# MIDI_CV_0_222.net
KiCad netlist of a schematic drawn in EAGLE
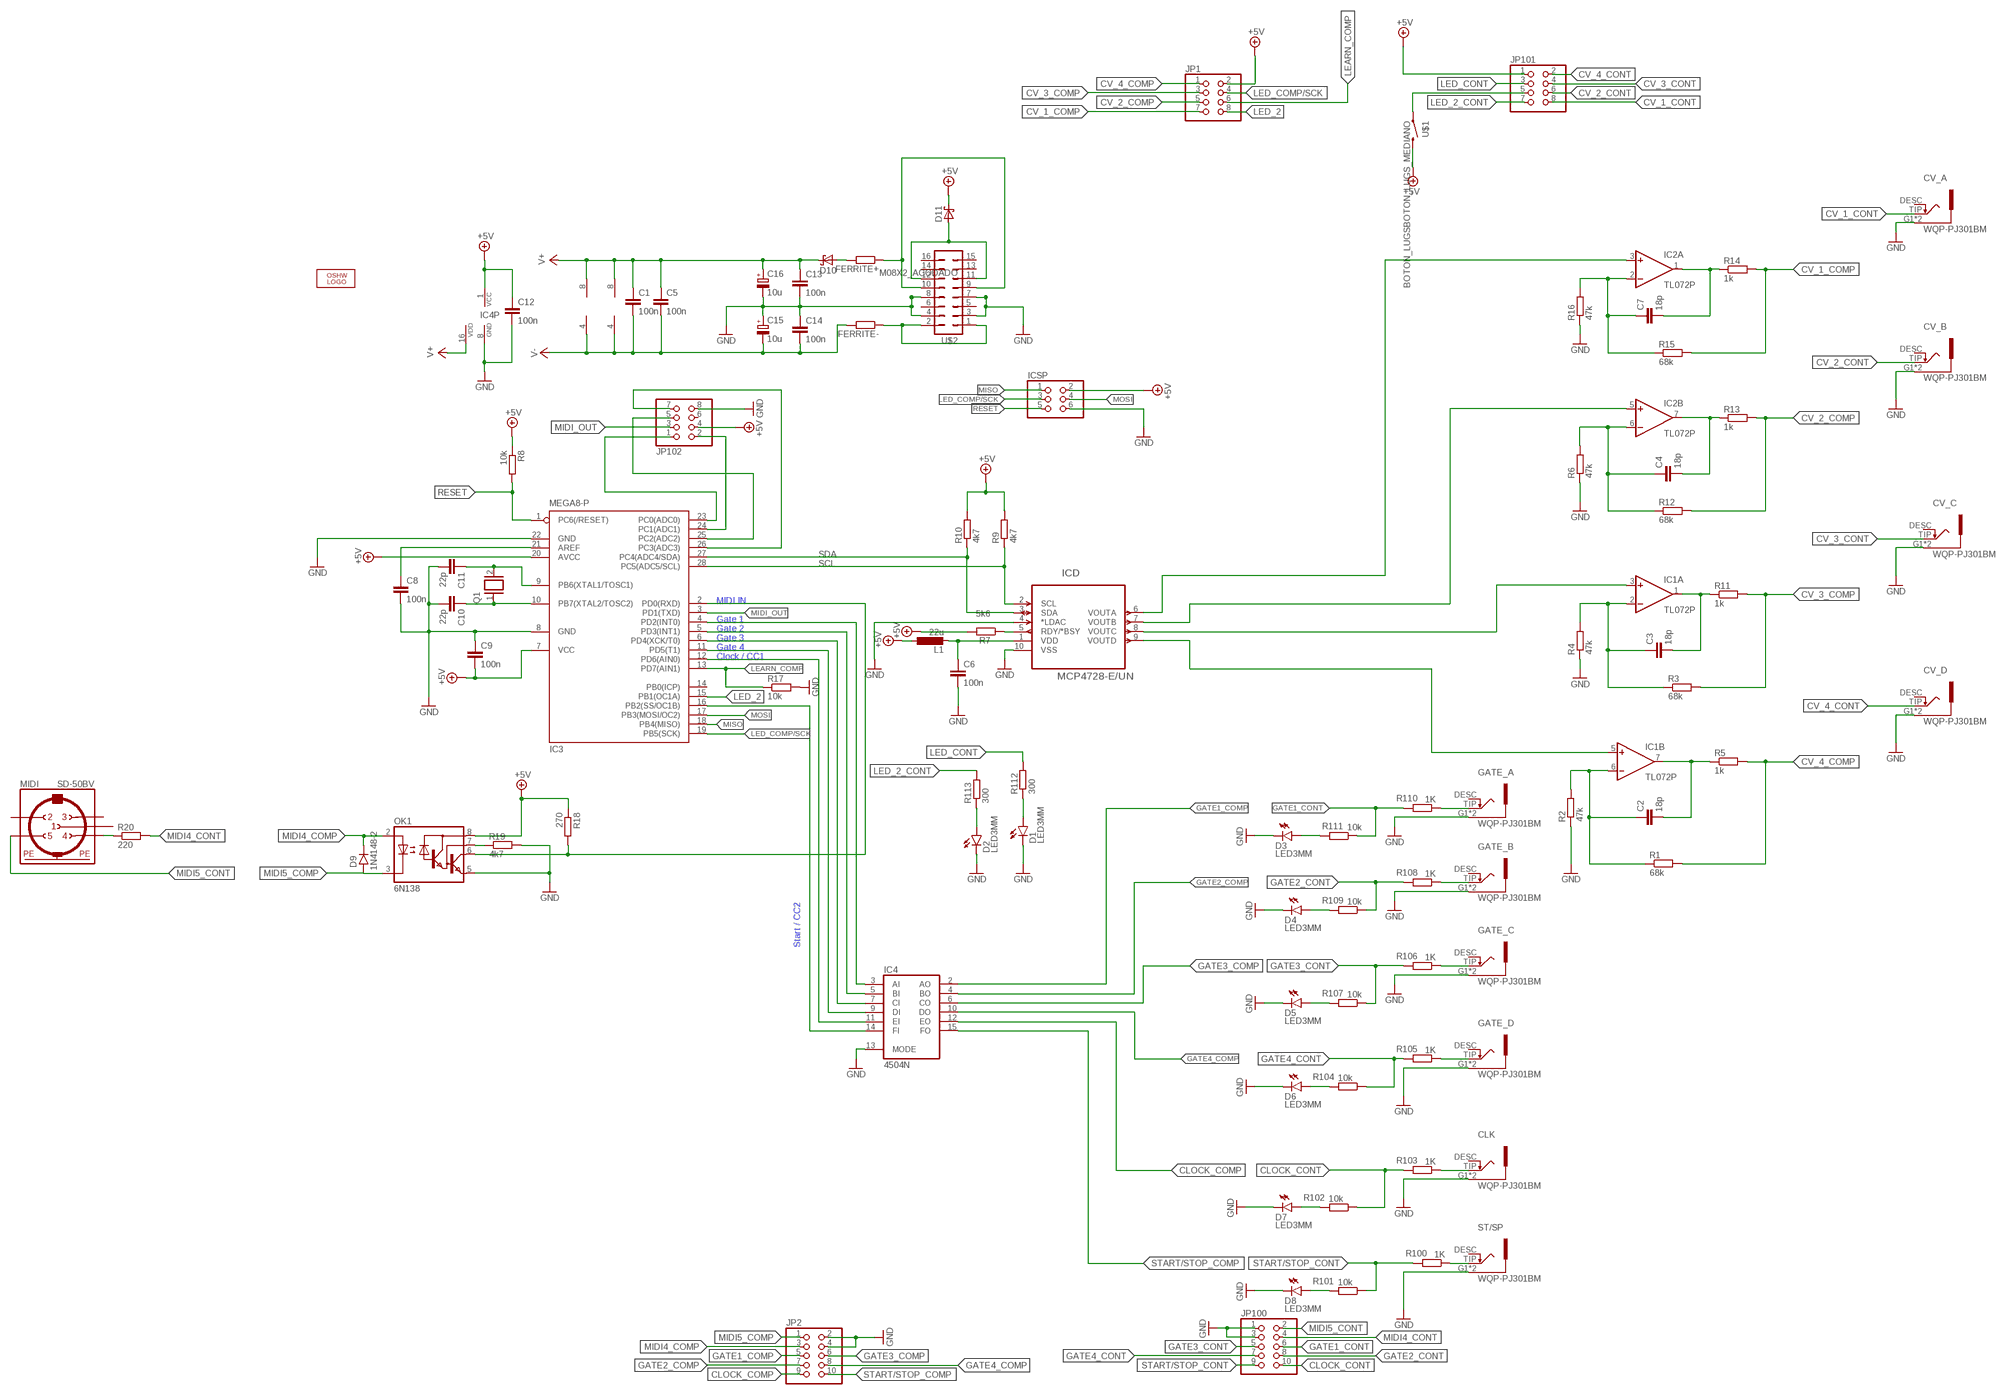
[diagram p0: schematic, sheet 1]

(export (version "E")
  (design (tool "Eeschema 10.0.6"))
  (components
    (comp (ref "$1_35_$")
      (value "OSHW_LOGO_FILLX0200-NT")
      (footprint "eagle-import:OSHW_FILLX200_NOTEXT")
      (libsource (lib "eagle-import") (part "OSHW_LOGO_FILLX0200-NT"))
    )
    (comp (ref "C1")
      (value "100n")
      (footprint "eagle-import:C050-025X075")
      (libsource (lib "eagle-import") (part "C-EU050-025X075"))
    )
    (comp (ref "C2")
      (value "18p")
      (footprint "eagle-import:C050-025X075")
      (libsource (lib "eagle-import") (part "C-EU050-025X075"))
    )
    (comp (ref "C3")
      (value "18p")
      (footprint "eagle-import:C050-025X075")
      (libsource (lib "eagle-import") (part "C-EU050-025X075"))
    )
    (comp (ref "C4")
      (value "18p")
      (footprint "eagle-import:C050-025X075")
      (libsource (lib "eagle-import") (part "C-EU050-025X075"))
    )
    (comp (ref "C5")
      (value "100n")
      (footprint "eagle-import:C050-025X075")
      (libsource (lib "eagle-import") (part "C-EU050-025X075"))
    )
    (comp (ref "C6")
      (value "100n")
      (footprint "eagle-import:C050-025X075")
      (libsource (lib "eagle-import") (part "C-EU050-025X075"))
    )
    (comp (ref "C7")
      (value "18p")
      (footprint "eagle-import:C050-025X075")
      (libsource (lib "eagle-import") (part "C-EU050-025X075"))
    )
    (comp (ref "C8")
      (value "100n")
      (footprint "eagle-import:C050-025X075")
      (libsource (lib "eagle-import") (part "C-EU050-025X075"))
    )
    (comp (ref "C9")
      (value "100n")
      (footprint "eagle-import:C050-025X075")
      (libsource (lib "eagle-import") (part "C-EU050-025X075"))
    )
    (comp (ref "C10")
      (value "22p")
      (footprint "eagle-import:C050-025X075")
      (libsource (lib "eagle-import") (part "C-EU050-025X075"))
    )
    (comp (ref "C11")
      (value "22p")
      (footprint "eagle-import:C050-025X075")
      (libsource (lib "eagle-import") (part "C-EU050-025X075"))
    )
    (comp (ref "C12")
      (value "100n")
      (footprint "eagle-import:C050-025X075")
      (libsource (lib "eagle-import") (part "C-EU050-025X075"))
    )
    (comp (ref "C13")
      (value "100n")
      (footprint "eagle-import:C050-025X075")
      (libsource (lib "eagle-import") (part "C-EU050-025X075"))
    )
    (comp (ref "C14")
      (value "100n")
      (footprint "eagle-import:C050-025X075")
      (libsource (lib "eagle-import") (part "C-EU050-025X075"))
    )
    (comp (ref "C15")
      (value "10u")
      (footprint "eagle-import:E2-4")
      (libsource (lib "eagle-import") (part "CPOL-EUE2-4"))
    )
    (comp (ref "C16")
      (value "10u")
      (footprint "eagle-import:E2-4")
      (libsource (lib "eagle-import") (part "CPOL-EUE2-4"))
    )
    (comp (ref "CLK")
      (value "WQP-PJ301BM")
      (footprint "eagle-import:WQP-PJ301BM")
      (libsource (lib "eagle-import") (part "WQP-PJ301BM"))
    )
    (comp (ref "CV_A")
      (value "WQP-PJ301BM")
      (footprint "eagle-import:WQP-PJ301BM")
      (libsource (lib "eagle-import") (part "WQP-PJ301BM"))
    )
    (comp (ref "CV_B")
      (value "WQP-PJ301BM")
      (footprint "eagle-import:WQP-PJ301BM")
      (libsource (lib "eagle-import") (part "WQP-PJ301BM"))
    )
    (comp (ref "CV_C")
      (value "WQP-PJ301BM")
      (footprint "eagle-import:WQP-PJ301BM")
      (libsource (lib "eagle-import") (part "WQP-PJ301BM"))
    )
    (comp (ref "CV_D")
      (value "WQP-PJ301BM")
      (footprint "eagle-import:WQP-PJ301BM")
      (libsource (lib "eagle-import") (part "WQP-PJ301BM"))
    )
    (comp (ref "D1")
      (value "LED3MM")
      (footprint "eagle-import:LED3MM")
      (libsource (lib "eagle-import") (part "LED3MM"))
    )
    (comp (ref "D2")
      (value "LED3MM")
      (footprint "eagle-import:LED3MM")
      (libsource (lib "eagle-import") (part "LED3MM"))
    )
    (comp (ref "D3")
      (value "LED3MM")
      (footprint "eagle-import:LED3MM")
      (libsource (lib "eagle-import") (part "LED3MM"))
    )
    (comp (ref "D4")
      (value "LED3MM")
      (footprint "eagle-import:LED3MM")
      (libsource (lib "eagle-import") (part "LED3MM"))
    )
    (comp (ref "D5")
      (value "LED3MM")
      (footprint "eagle-import:LED3MM")
      (libsource (lib "eagle-import") (part "LED3MM"))
    )
    (comp (ref "D6")
      (value "LED3MM")
      (footprint "eagle-import:LED3MM")
      (libsource (lib "eagle-import") (part "LED3MM"))
    )
    (comp (ref "D7")
      (value "LED3MM")
      (footprint "eagle-import:LED3MM")
      (libsource (lib "eagle-import") (part "LED3MM"))
    )
    (comp (ref "D8")
      (value "LED3MM")
      (footprint "eagle-import:LED3MM")
      (libsource (lib "eagle-import") (part "LED3MM"))
    )
    (comp (ref "D9")
      (value "1N4148-2")
      (footprint "eagle-import:DO35-2")
      (libsource (lib "eagle-import") (part "1N4148-2"))
    )
    (comp (ref "D10")
      (value "SCHOTTKY-DIODEDO35-7")
      (footprint "eagle-import:DO35-7")
      (libsource (lib "eagle-import") (part "SCHOTTKY-DIODEDO35-7"))
    )
    (comp (ref "D11")
      (value "SCHOTTKY-DIODEDO35-7")
      (footprint "eagle-import:DO35-7")
      (libsource (lib "eagle-import") (part "SCHOTTKY-DIODEDO35-7"))
    )
    (comp (ref "FERRITE+")
      (value "R-EU_0204/5")
      (footprint "eagle-import:0204_5")
      (libsource (lib "eagle-import") (part "R-EU_0204/5"))
    )
    (comp (ref "FERRITE-")
      (value "R-EU_0204/5")
      (footprint "eagle-import:0204_5")
      (libsource (lib "eagle-import") (part "R-EU_0204/5"))
    )
    (comp (ref "GATE_A")
      (value "WQP-PJ301BM")
      (footprint "eagle-import:WQP-PJ301BM")
      (libsource (lib "eagle-import") (part "WQP-PJ301BM"))
    )
    (comp (ref "GATE_B")
      (value "WQP-PJ301BM")
      (footprint "eagle-import:WQP-PJ301BM")
      (libsource (lib "eagle-import") (part "WQP-PJ301BM"))
    )
    (comp (ref "GATE_C")
      (value "WQP-PJ301BM")
      (footprint "eagle-import:WQP-PJ301BM")
      (libsource (lib "eagle-import") (part "WQP-PJ301BM"))
    )
    (comp (ref "GATE_D")
      (value "WQP-PJ301BM")
      (footprint "eagle-import:WQP-PJ301BM")
      (libsource (lib "eagle-import") (part "WQP-PJ301BM"))
    )
    (comp (ref "IC1")
      (value "TL072P")
      (footprint "eagle-import:DIL08")
      (libsource (lib "eagle-import") (part "TL072P"))
    )
    (comp (ref "IC2")
      (value "TL072P")
      (footprint "eagle-import:DIL08")
      (libsource (lib "eagle-import") (part "TL072P"))
    )
    (comp (ref "IC3")
      (value "MEGA8-P")
      (footprint "eagle-import:DIL28-3")
      (libsource (lib "eagle-import") (part "MEGA8-P"))
    )
    (comp (ref "IC4")
      (value "4504N")
      (footprint "eagle-import:DIL16")
      (libsource (lib "eagle-import") (part "4504N"))
    )
    (comp (ref "ICD")
      (value "MCP4728-E/UN")
      (footprint "eagle-import:SOP50P490X110-10N")
      (libsource (lib "eagle-import") (part "MCP4728-E/UN"))
    )
    (comp (ref "ICSP")
      (value "PINHD-2X3")
      (footprint "eagle-import:2X03")
      (libsource (lib "eagle-import") (part "PINHD-2X3"))
    )
    (comp (ref "JP1")
      (value "PINHD-2X4")
      (footprint "eagle-import:2X04")
      (libsource (lib "eagle-import") (part "PINHD-2X4"))
    )
    (comp (ref "JP2")
      (value "PINHD-2X5")
      (footprint "eagle-import:2X05")
      (libsource (lib "eagle-import") (part "PINHD-2X5"))
    )
    (comp (ref "JP100")
      (value "PINHD-2X5")
      (footprint "eagle-import:2X05")
      (libsource (lib "eagle-import") (part "PINHD-2X5"))
    )
    (comp (ref "JP101")
      (value "PINHD-2X4")
      (footprint "eagle-import:2X04")
      (libsource (lib "eagle-import") (part "PINHD-2X4"))
    )
    (comp (ref "JP102")
      (value "PINHD-2X4")
      (footprint "eagle-import:2X04")
      (libsource (lib "eagle-import") (part "PINHD-2X4"))
    )
    (comp (ref "L1")
      (value "22u")
      (footprint "eagle-import:0204_7")
      (libsource (lib "eagle-import") (part "L-EU0204/7"))
    )
    (comp (ref "MIDI")
      (value "SD-50BV")
      (footprint "eagle-import:SD-50BV")
      (libsource (lib "eagle-import") (part "SD-50BV"))
    )
    (comp (ref "OK1")
      (value "6N138")
      (footprint "eagle-import:DIL08")
      (libsource (lib "eagle-import") (part "6N138"))
    )
    (comp (ref "Q1")
      (value "XTAL/S")
      (footprint "eagle-import:QS")
      (libsource (lib "eagle-import") (part "XTAL/S"))
    )
    (comp (ref "R1")
      (value "68k")
      (footprint "eagle-import:0204_5")
      (libsource (lib "eagle-import") (part "R-EU_0204/5"))
    )
    (comp (ref "R2")
      (value "47k")
      (footprint "eagle-import:0204_5")
      (libsource (lib "eagle-import") (part "R-EU_0204/5"))
    )
    (comp (ref "R3")
      (value "68k")
      (footprint "eagle-import:0204_5")
      (libsource (lib "eagle-import") (part "R-EU_0204/5"))
    )
    (comp (ref "R4")
      (value "47k")
      (footprint "eagle-import:0204_5")
      (libsource (lib "eagle-import") (part "R-EU_0204/5"))
    )
    (comp (ref "R5")
      (value "1k")
      (footprint "eagle-import:0204_5")
      (libsource (lib "eagle-import") (part "R-EU_0204/5"))
    )
    (comp (ref "R6")
      (value "47k")
      (footprint "eagle-import:0204_5")
      (libsource (lib "eagle-import") (part "R-EU_0204/5"))
    )
    (comp (ref "R7")
      (value "5k6")
      (footprint "eagle-import:0204_5")
      (libsource (lib "eagle-import") (part "R-EU_0204/5"))
    )
    (comp (ref "R8")
      (value "10k")
      (footprint "eagle-import:0204_5")
      (libsource (lib "eagle-import") (part "R-EU_0204/5"))
    )
    (comp (ref "R9")
      (value "4k7")
      (footprint "eagle-import:0204_5")
      (libsource (lib "eagle-import") (part "R-EU_0204/5"))
    )
    (comp (ref "R10")
      (value "4k7")
      (footprint "eagle-import:0204_5")
      (libsource (lib "eagle-import") (part "R-EU_0204/5"))
    )
    (comp (ref "R11")
      (value "1k")
      (footprint "eagle-import:0204_5")
      (libsource (lib "eagle-import") (part "R-EU_0204/5"))
    )
    (comp (ref "R12")
      (value "68k")
      (footprint "eagle-import:0204_5")
      (libsource (lib "eagle-import") (part "R-EU_0204/5"))
    )
    (comp (ref "R13")
      (value "1k")
      (footprint "eagle-import:0204_5")
      (libsource (lib "eagle-import") (part "R-EU_0204/5"))
    )
    (comp (ref "R14")
      (value "1k")
      (footprint "eagle-import:0204_5")
      (libsource (lib "eagle-import") (part "R-EU_0204/5"))
    )
    (comp (ref "R15")
      (value "68k")
      (footprint "eagle-import:0204_5")
      (libsource (lib "eagle-import") (part "R-EU_0204/5"))
    )
    (comp (ref "R16")
      (value "47k")
      (footprint "eagle-import:0204_5")
      (libsource (lib "eagle-import") (part "R-EU_0204/5"))
    )
    (comp (ref "R17")
      (value "10k")
      (footprint "eagle-import:0204_5")
      (libsource (lib "eagle-import") (part "R-EU_0204/5"))
    )
    (comp (ref "R18")
      (value "270")
      (footprint "eagle-import:0204_5")
      (libsource (lib "eagle-import") (part "R-EU_0204/5"))
    )
    (comp (ref "R19")
      (value "4k7")
      (footprint "eagle-import:0204_5")
      (libsource (lib "eagle-import") (part "R-EU_0204/5"))
    )
    (comp (ref "R20")
      (value "220")
      (footprint "eagle-import:0204_5")
      (libsource (lib "eagle-import") (part "R-EU_0204/5"))
    )
    (comp (ref "R100")
      (value "1K")
      (footprint "eagle-import:0204_5")
      (libsource (lib "eagle-import") (part "R-EU_0204/5"))
    )
    (comp (ref "R101")
      (value "10k")
      (footprint "eagle-import:0204_5")
      (libsource (lib "eagle-import") (part "R-EU_0204/5"))
    )
    (comp (ref "R102")
      (value "10k")
      (footprint "eagle-import:0204_5")
      (libsource (lib "eagle-import") (part "R-EU_0204/5"))
    )
    (comp (ref "R103")
      (value "1K")
      (footprint "eagle-import:0204_5")
      (libsource (lib "eagle-import") (part "R-EU_0204/5"))
    )
    (comp (ref "R104")
      (value "10k")
      (footprint "eagle-import:0204_5")
      (libsource (lib "eagle-import") (part "R-EU_0204/5"))
    )
    (comp (ref "R105")
      (value "1K")
      (footprint "eagle-import:0204_5")
      (libsource (lib "eagle-import") (part "R-EU_0204/5"))
    )
    (comp (ref "R106")
      (value "1K")
      (footprint "eagle-import:0204_5")
      (libsource (lib "eagle-import") (part "R-EU_0204/5"))
    )
    (comp (ref "R107")
      (value "10k")
      (footprint "eagle-import:0204_5")
      (libsource (lib "eagle-import") (part "R-EU_0204/5"))
    )
    (comp (ref "R108")
      (value "1K")
      (footprint "eagle-import:0204_5")
      (libsource (lib "eagle-import") (part "R-EU_0204/5"))
    )
    (comp (ref "R109")
      (value "10k")
      (footprint "eagle-import:0204_5")
      (libsource (lib "eagle-import") (part "R-EU_0204/5"))
    )
    (comp (ref "R110")
      (value "1K")
      (footprint "eagle-import:0204_5")
      (libsource (lib "eagle-import") (part "R-EU_0204/5"))
    )
    (comp (ref "R111")
      (value "10k")
      (footprint "eagle-import:0204_5")
      (libsource (lib "eagle-import") (part "R-EU_0204/5"))
    )
    (comp (ref "R112")
      (value "300")
      (footprint "eagle-import:0204_5")
      (libsource (lib "eagle-import") (part "R-EU_0204/5"))
    )
    (comp (ref "R113")
      (value "300")
      (footprint "eagle-import:0204_5")
      (libsource (lib "eagle-import") (part "R-EU_0204/5"))
    )
    (comp (ref "ST/SP")
      (value "WQP-PJ301BM")
      (footprint "eagle-import:WQP-PJ301BM")
      (libsource (lib "eagle-import") (part "WQP-PJ301BM"))
    )
    (comp (ref "U$1")
      (value "BOTON_LUGSBOTON_LUGS_MEDIANO")
      (footprint "eagle-import:BOTON_LUGS_MEDIANO")
      (libsource (lib "eagle-import") (part "BOTON_LUGSBOTON_LUGS_MEDIANO"))
    )
    (comp (ref "U$2")
      (value "M08X2_ACODADO")
      (footprint "eagle-import:2X8-POWER-ACODADO")
      (libsource (lib "eagle-import") (part "M08X2_ACODADO"))
    )
  )
  (nets
    (net (code "1") (name "+5V") (class "Default")
      (node (ref "C12") (pin "1") (pinfunction "1_1") (pintype "passive"))
      (node (ref "C9") (pin "2") (pinfunction "2_2") (pintype "passive"))
      (node (ref "D11") (pin "C") (pinfunction "C_C") (pintype "passive"))
      (node (ref "IC3") (pin "20") (pinfunction "AVCC_20") (pintype "power_in"))
      (node (ref "IC3") (pin "7") (pinfunction "VCC_7") (pintype "power_in"))
      (node (ref "IC4") (pin "1") (pinfunction "VCC_1") (pintype "power_in"))
      (node (ref "ICSP") (pin "2") (pinfunction "2_2") (pintype "passive"))
      (node (ref "JP1") (pin "2") (pinfunction "2_2") (pintype "passive"))
      (node (ref "JP101") (pin "1") (pinfunction "1_1") (pintype "passive"))
      (node (ref "JP102") (pin "4") (pinfunction "4_4") (pintype "passive"))
      (node (ref "L1") (pin "1") (pinfunction "1_1") (pintype "passive"))
      (node (ref "OK1") (pin "8") (pinfunction "VCC_8") (pintype "passive"))
      (node (ref "R10") (pin "2") (pinfunction "2_2") (pintype "passive"))
      (node (ref "R18") (pin "1") (pinfunction "1_1") (pintype "passive"))
      (node (ref "R7") (pin "2") (pinfunction "2_2") (pintype "passive"))
      (node (ref "R8") (pin "1") (pinfunction "1_1") (pintype "passive"))
      (node (ref "R9") (pin "2") (pinfunction "2_2") (pintype "passive"))
      (node (ref "U$1") (pin "P$2") (pinfunction "2_P$2") (pintype "passive"))
    )
    (net (code "2") (name "CLOCK_COMP") (class "Default")
      (node (ref "IC4") (pin "12") (pinfunction "EO_12") (pintype "output"))
      (node (ref "JP2") (pin "9") (pinfunction "9_9") (pintype "passive"))
    )
    (net (code "3") (name "CLOCK_CONT") (class "Default")
      (node (ref "JP100") (pin "10") (pinfunction "10_10") (pintype "passive"))
      (node (ref "R102") (pin "1") (pinfunction "1_1") (pintype "passive"))
      (node (ref "R103") (pin "2") (pinfunction "2_2") (pintype "passive"))
    )
    (net (code "4") (name "CV_1_COMP") (class "Default")
      (node (ref "JP1") (pin "7") (pinfunction "7_7") (pintype "passive"))
      (node (ref "R14") (pin "2") (pinfunction "2_2") (pintype "passive"))
      (node (ref "R15") (pin "2") (pinfunction "2_2") (pintype "passive"))
    )
    (net (code "5") (name "CV_1_CONT") (class "Default")
      (node (ref "CV_A") (pin "TIP") (pinfunction "TIP_TIP") (pintype "passive"))
      (node (ref "JP101") (pin "8") (pinfunction "8_8") (pintype "passive"))
    )
    (net (code "6") (name "CV_2_COMP") (class "Default")
      (node (ref "JP1") (pin "5") (pinfunction "5_5") (pintype "passive"))
      (node (ref "R12") (pin "2") (pinfunction "2_2") (pintype "passive"))
      (node (ref "R13") (pin "2") (pinfunction "2_2") (pintype "passive"))
    )
    (net (code "7") (name "CV_2_CONT") (class "Default")
      (node (ref "CV_B") (pin "TIP") (pinfunction "TIP_TIP") (pintype "passive"))
      (node (ref "JP101") (pin "6") (pinfunction "6_6") (pintype "passive"))
    )
    (net (code "8") (name "CV_3_COMP") (class "Default")
      (node (ref "JP1") (pin "3") (pinfunction "3_3") (pintype "passive"))
      (node (ref "R11") (pin "2") (pinfunction "2_2") (pintype "passive"))
      (node (ref "R3") (pin "2") (pinfunction "2_2") (pintype "passive"))
    )
    (net (code "9") (name "CV_3_CONT") (class "Default")
      (node (ref "CV_C") (pin "TIP") (pinfunction "TIP_TIP") (pintype "passive"))
      (node (ref "JP101") (pin "4") (pinfunction "4_4") (pintype "passive"))
    )
    (net (code "10") (name "CV_4_COMP") (class "Default")
      (node (ref "JP1") (pin "1") (pinfunction "1_1") (pintype "passive"))
      (node (ref "R1") (pin "2") (pinfunction "2_2") (pintype "passive"))
      (node (ref "R5") (pin "2") (pinfunction "2_2") (pintype "passive"))
    )
    (net (code "11") (name "CV_4_CONT") (class "Default")
      (node (ref "CV_D") (pin "TIP") (pinfunction "TIP_TIP") (pintype "passive"))
      (node (ref "JP101") (pin "2") (pinfunction "2_2") (pintype "passive"))
    )
    (net (code "12") (name "GATE1_COMP") (class "Default")
      (node (ref "IC4") (pin "2") (pinfunction "AO_2") (pintype "output"))
      (node (ref "JP2") (pin "5") (pinfunction "5_5") (pintype "passive"))
    )
    (net (code "13") (name "GATE1_CONT") (class "Default")
      (node (ref "JP100") (pin "6") (pinfunction "6_6") (pintype "passive"))
      (node (ref "R110") (pin "2") (pinfunction "2_2") (pintype "passive"))
      (node (ref "R111") (pin "1") (pinfunction "1_1") (pintype "passive"))
    )
    (net (code "14") (name "GATE2_COMP") (class "Default")
      (node (ref "IC4") (pin "4") (pinfunction "BO_4") (pintype "output"))
      (node (ref "JP2") (pin "7") (pinfunction "7_7") (pintype "passive"))
    )
    (net (code "15") (name "GATE2_CONT") (class "Default")
      (node (ref "JP100") (pin "8") (pinfunction "8_8") (pintype "passive"))
      (node (ref "R108") (pin "2") (pinfunction "2_2") (pintype "passive"))
      (node (ref "R109") (pin "1") (pinfunction "1_1") (pintype "passive"))
    )
    (net (code "16") (name "GATE3_COMP") (class "Default")
      (node (ref "IC4") (pin "6") (pinfunction "CO_6") (pintype "output"))
      (node (ref "JP2") (pin "6") (pinfunction "6_6") (pintype "passive"))
    )
    (net (code "17") (name "GATE3_CONT") (class "Default")
      (node (ref "JP100") (pin "5") (pinfunction "5_5") (pintype "passive"))
      (node (ref "R106") (pin "2") (pinfunction "2_2") (pintype "passive"))
      (node (ref "R107") (pin "1") (pinfunction "1_1") (pintype "passive"))
    )
    (net (code "18") (name "GATE4_COMP") (class "Default")
      (node (ref "IC4") (pin "10") (pinfunction "DO_10") (pintype "output"))
      (node (ref "JP2") (pin "8") (pinfunction "8_8") (pintype "passive"))
    )
    (net (code "19") (name "GATE4_CONT") (class "Default")
      (node (ref "JP100") (pin "7") (pinfunction "7_7") (pintype "passive"))
      (node (ref "R104") (pin "1") (pinfunction "1_1") (pintype "passive"))
      (node (ref "R105") (pin "2") (pinfunction "2_2") (pintype "passive"))
    )
    (net (code "20") (name "GND") (class "Default")
      (node (ref "C10") (pin "2") (pinfunction "2_2") (pintype "passive"))
      (node (ref "C11") (pin "2") (pinfunction "2_2") (pintype "passive"))
      (node (ref "C12") (pin "2") (pinfunction "2_2") (pintype "passive"))
      (node (ref "C13") (pin "2") (pinfunction "2_2") (pintype "passive"))
      (node (ref "C14") (pin "1") (pinfunction "1_1") (pintype "passive"))
      (node (ref "C15") (pin "+") (pinfunction "+_+") (pintype "passive"))
      (node (ref "C16") (pin "-") (pinfunction "-_-") (pintype "passive"))
      (node (ref "C6") (pin "2") (pinfunction "2_2") (pintype "passive"))
      (node (ref "C8") (pin "2") (pinfunction "2_2") (pintype "passive"))
      (node (ref "C9") (pin "1") (pinfunction "1_1") (pintype "passive"))
      (node (ref "CLK") (pin "G1") (pinfunction "SLEVE_G1") (pintype "passive"))
      (node (ref "CLK") (pin "G2") (pinfunction "SLEVE_G2") (pintype "passive"))
      (node (ref "CV_A") (pin "G1") (pinfunction "SLEVE_G1") (pintype "passive"))
      (node (ref "CV_A") (pin "G2") (pinfunction "SLEVE_G2") (pintype "passive"))
      (node (ref "CV_B") (pin "G1") (pinfunction "SLEVE_G1") (pintype "passive"))
      (node (ref "CV_B") (pin "G2") (pinfunction "SLEVE_G2") (pintype "passive"))
      (node (ref "CV_C") (pin "G1") (pinfunction "SLEVE_G1") (pintype "passive"))
      (node (ref "CV_C") (pin "G2") (pinfunction "SLEVE_G2") (pintype "passive"))
      (node (ref "CV_D") (pin "G1") (pinfunction "SLEVE_G1") (pintype "passive"))
      (node (ref "CV_D") (pin "G2") (pinfunction "SLEVE_G2") (pintype "passive"))
      (node (ref "D1") (pin "K") (pinfunction "C_K") (pintype "passive"))
      (node (ref "D2") (pin "K") (pinfunction "C_K") (pintype "passive"))
      (node (ref "D3") (pin "K") (pinfunction "C_K") (pintype "passive"))
      (node (ref "D4") (pin "K") (pinfunction "C_K") (pintype "passive"))
      (node (ref "D5") (pin "K") (pinfunction "C_K") (pintype "passive"))
      (node (ref "D6") (pin "K") (pinfunction "C_K") (pintype "passive"))
      (node (ref "D7") (pin "K") (pinfunction "C_K") (pintype "passive"))
      (node (ref "D8") (pin "K") (pinfunction "C_K") (pintype "passive"))
      (node (ref "GATE_A") (pin "G1") (pinfunction "SLEVE_G1") (pintype "passive"))
      (node (ref "GATE_A") (pin "G2") (pinfunction "SLEVE_G2") (pintype "passive"))
      (node (ref "GATE_B") (pin "G1") (pinfunction "SLEVE_G1") (pintype "passive"))
      (node (ref "GATE_B") (pin "G2") (pinfunction "SLEVE_G2") (pintype "passive"))
      (node (ref "GATE_C") (pin "G1") (pinfunction "SLEVE_G1") (pintype "passive"))
      (node (ref "GATE_C") (pin "G2") (pinfunction "SLEVE_G2") (pintype "passive"))
      (node (ref "GATE_D") (pin "G1") (pinfunction "SLEVE_G1") (pintype "passive"))
      (node (ref "GATE_D") (pin "G2") (pinfunction "SLEVE_G2") (pintype "passive"))
      (node (ref "IC3") (pin "22") (pinfunction "GND_22") (pintype "power_in"))
      (node (ref "IC3") (pin "8") (pinfunction "GND_8") (pintype "power_in"))
      (node (ref "IC4") (pin "13") (pinfunction "MODE_13") (pintype "input"))
      (node (ref "IC4") (pin "8") (pinfunction "GND_8") (pintype "power_in"))
      (node (ref "ICD") (pin "10") (pinfunction "VSS_10") (pintype "power_in"))
      (node (ref "ICD") (pin "4") (pinfunction "*LDAC_4") (pintype "input"))
      (node (ref "ICSP") (pin "6") (pinfunction "6_6") (pintype "passive"))
      (node (ref "JP100") (pin "1") (pinfunction "1_1") (pintype "passive"))
      (node (ref "JP100") (pin "3") (pinfunction "3_3") (pintype "passive"))
      (node (ref "JP102") (pin "8") (pinfunction "8_8") (pintype "passive"))
      (node (ref "JP2") (pin "2") (pinfunction "2_2") (pintype "passive"))
      (node (ref "JP2") (pin "4") (pinfunction "4_4") (pintype "passive"))
      (node (ref "OK1") (pin "5") (pinfunction "GND_5") (pintype "passive"))
      (node (ref "R16") (pin "1") (pinfunction "1_1") (pintype "passive"))
      (node (ref "R17") (pin "2") (pinfunction "2_2") (pintype "passive"))
      (node (ref "R19") (pin "2") (pinfunction "2_2") (pintype "passive"))
      (node (ref "R2") (pin "1") (pinfunction "1_1") (pintype "passive"))
      (node (ref "R4") (pin "1") (pinfunction "1_1") (pintype "passive"))
      (node (ref "R6") (pin "1") (pinfunction "1_1") (pintype "passive"))
      (node (ref "ST/SP") (pin "G1") (pinfunction "SLEVE_G1") (pintype "passive"))
      (node (ref "ST/SP") (pin "G2") (pinfunction "SLEVE_G2") (pintype "passive"))
      (node (ref "U$2") (pin "3") (pinfunction "3_3") (pintype "passive"))
      (node (ref "U$2") (pin "4") (pinfunction "4_4") (pintype "passive"))
      (node (ref "U$2") (pin "7") (pinfunction "7_7") (pintype "passive"))
      (node (ref "U$2") (pin "8") (pinfunction "8_8") (pintype "passive"))
    )
    (net (code "21") (name "LEARN_COMP") (class "Default")
      (node (ref "IC3") (pin "13") (pinfunction "PD7(AIN1)_13") (pintype "bidirectional"))
      (node (ref "JP1") (pin "6") (pinfunction "6_6") (pintype "passive"))
      (node (ref "R17") (pin "1") (pinfunction "1_1") (pintype "passive"))
    )
    (net (code "22") (name "LED_2") (class "Default")
      (node (ref "IC3") (pin "15") (pinfunction "PB1(OC1A)_15") (pintype "bidirectional"))
      (node (ref "JP1") (pin "8") (pinfunction "8_8") (pintype "passive"))
    )
    (net (code "23") (name "LED_2_CONT") (class "Default")
      (node (ref "JP101") (pin "7") (pinfunction "7_7") (pintype "passive"))
      (node (ref "R113") (pin "2") (pinfunction "2_2") (pintype "passive"))
    )
    (net (code "24") (name "LED_COMP{slash}SCK") (class "Default")
      (node (ref "IC3") (pin "19") (pinfunction "PB5(SCK)_19") (pintype "bidirectional"))
      (node (ref "ICSP") (pin "3") (pinfunction "3_3") (pintype "passive"))
      (node (ref "JP1") (pin "4") (pinfunction "4_4") (pintype "passive"))
    )
    (net (code "25") (name "LED_CONT") (class "Default")
      (node (ref "JP101") (pin "3") (pinfunction "3_3") (pintype "passive"))
      (node (ref "R112") (pin "2") (pinfunction "2_2") (pintype "passive"))
    )
    (net (code "26") (name "MIDI4_COMP") (class "Default")
      (node (ref "D9") (pin "C") (pinfunction "C_C") (pintype "passive"))
      (node (ref "JP2") (pin "3") (pinfunction "3_3") (pintype "passive"))
      (node (ref "OK1") (pin "2") (pinfunction "A_2") (pintype "passive"))
    )
    (net (code "27") (name "MIDI4_CONT") (class "Default")
      (node (ref "JP100") (pin "4") (pinfunction "4_4") (pintype "passive"))
      (node (ref "R20") (pin "2") (pinfunction "2_2") (pintype "passive"))
    )
    (net (code "28") (name "MIDI5_COMP") (class "Default")
      (node (ref "D9") (pin "A") (pinfunction "A_A") (pintype "passive"))
      (node (ref "JP2") (pin "1") (pinfunction "1_1") (pintype "passive"))
      (node (ref "OK1") (pin "3") (pinfunction "C_3") (pintype "passive"))
    )
    (net (code "29") (name "MIDI5_CONT") (class "Default")
      (node (ref "JP100") (pin "2") (pinfunction "2_2") (pintype "passive"))
      (node (ref "MIDI") (pin "5") (pinfunction "5_5") (pintype "passive"))
    )
    (net (code "30") (name "MIDI_OUT") (class "Default")
      (node (ref "IC3") (pin "3") (pinfunction "PD1(TXD)_3") (pintype "bidirectional"))
      (node (ref "JP102") (pin "3") (pinfunction "3_3") (pintype "passive"))
    )
    (net (code "31") (name "MISO") (class "Default")
      (node (ref "IC3") (pin "18") (pinfunction "PB4(MISO)_18") (pintype "bidirectional"))
      (node (ref "ICSP") (pin "1") (pinfunction "1_1") (pintype "passive"))
    )
    (net (code "32") (name "MOSI") (class "Default")
      (node (ref "IC3") (pin "17") (pinfunction "PB3(MOSI/OC2)_17") (pintype "bidirectional"))
      (node (ref "ICSP") (pin "4") (pinfunction "4_4") (pintype "passive"))
    )
    (net (code "33") (name "Net-(CLK-PadTIP)") (class "Default")
      (node (ref "CLK") (pin "TIP") (pinfunction "TIP_TIP") (pintype "passive"))
      (node (ref "R103") (pin "1") (pinfunction "1_1") (pintype "passive"))
    )
    (net (code "34") (name "Net-(D1-PadA)") (class "Default")
      (node (ref "D1") (pin "A") (pinfunction "A_A") (pintype "passive"))
      (node (ref "R112") (pin "1") (pinfunction "1_1") (pintype "passive"))
    )
    (net (code "35") (name "Net-(D2-PadA)") (class "Default")
      (node (ref "D2") (pin "A") (pinfunction "A_A") (pintype "passive"))
      (node (ref "R113") (pin "1") (pinfunction "1_1") (pintype "passive"))
    )
    (net (code "36") (name "Net-(D3-PadA)") (class "Default")
      (node (ref "D3") (pin "A") (pinfunction "A_A") (pintype "passive"))
      (node (ref "R111") (pin "2") (pinfunction "2_2") (pintype "passive"))
    )
    (net (code "37") (name "Net-(D4-PadA)") (class "Default")
      (node (ref "D4") (pin "A") (pinfunction "A_A") (pintype "passive"))
      (node (ref "R109") (pin "2") (pinfunction "2_2") (pintype "passive"))
    )
    (net (code "38") (name "Net-(D5-PadA)") (class "Default")
      (node (ref "D5") (pin "A") (pinfunction "A_A") (pintype "passive"))
      (node (ref "R107") (pin "2") (pinfunction "2_2") (pintype "passive"))
    )
    (net (code "39") (name "Net-(D6-PadA)") (class "Default")
      (node (ref "D6") (pin "A") (pinfunction "A_A") (pintype "passive"))
      (node (ref "R104") (pin "2") (pinfunction "2_2") (pintype "passive"))
    )
    (net (code "40") (name "Net-(D7-PadA)") (class "Default")
      (node (ref "D7") (pin "A") (pinfunction "A_A") (pintype "passive"))
      (node (ref "R102") (pin "2") (pinfunction "2_2") (pintype "passive"))
    )
    (net (code "41") (name "Net-(D8-PadA)") (class "Default")
      (node (ref "D8") (pin "A") (pinfunction "A_A") (pintype "passive"))
      (node (ref "R101") (pin "2") (pinfunction "2_2") (pintype "passive"))
    )
    (net (code "42") (name "Net-(D10-PadA)") (class "Default")
      (node (ref "D10") (pin "A") (pinfunction "A_A") (pintype "passive"))
      (node (ref "FERRITE+") (pin "2") (pinfunction "2_2") (pintype "passive"))
    )
    (net (code "43") (name "Net-(D11-PadA)") (class "Default")
      (node (ref "D11") (pin "A") (pinfunction "A_A") (pintype "passive"))
      (node (ref "U$2") (pin "11") (pinfunction "11_11") (pintype "passive"))
      (node (ref "U$2") (pin "12") (pinfunction "12_12") (pintype "passive"))
    )
    (net (code "44") (name "Net-(FERRITE+-Pad1)") (class "Default")
      (node (ref "FERRITE+") (pin "1") (pinfunction "1_1") (pintype "passive"))
      (node (ref "U$2") (pin "10") (pinfunction "10_10") (pintype "passive"))
      (node (ref "U$2") (pin "9") (pinfunction "9_9") (pintype "passive"))
    )
    (net (code "45") (name "Net-(FERRITE--Pad1)") (class "Default")
      (node (ref "FERRITE-") (pin "1") (pinfunction "1_1") (pintype "passive"))
      (node (ref "U$2") (pin "1") (pinfunction "1_1") (pintype "passive"))
      (node (ref "U$2") (pin "2") (pinfunction "2_2") (pintype "passive"))
    )
    (net (code "46") (name "Net-(GATE_A-PadTIP)") (class "Default")
      (node (ref "GATE_A") (pin "TIP") (pinfunction "TIP_TIP") (pintype "passive"))
      (node (ref "R110") (pin "1") (pinfunction "1_1") (pintype "passive"))
    )
    (net (code "47") (name "Net-(GATE_B-PadTIP)") (class "Default")
      (node (ref "GATE_B") (pin "TIP") (pinfunction "TIP_TIP") (pintype "passive"))
      (node (ref "R108") (pin "1") (pinfunction "1_1") (pintype "passive"))
    )
    (net (code "48") (name "Net-(GATE_C-PadTIP)") (class "Default")
      (node (ref "GATE_C") (pin "TIP") (pinfunction "TIP_TIP") (pintype "passive"))
      (node (ref "R106") (pin "1") (pinfunction "1_1") (pintype "passive"))
    )
    (net (code "49") (name "Net-(GATE_D-PadTIP)") (class "Default")
      (node (ref "GATE_D") (pin "TIP") (pinfunction "TIP_TIP") (pintype "passive"))
      (node (ref "R105") (pin "1") (pinfunction "1_1") (pintype "passive"))
    )
    (net (code "50") (name "Net-(IC1A-+IN)") (class "Default")
      (node (ref "IC1") (pin "3") (pinfunction "+IN_3") (pintype "input"))
      (node (ref "ICD") (pin "8") (pinfunction "VOUTC_8") (pintype "output"))
    )
    (net (code "51") (name "Net-(IC1A--IN)") (class "Default")
      (node (ref "C3") (pin "1") (pinfunction "1_1") (pintype "passive"))
      (node (ref "IC1") (pin "2") (pinfunction "-IN_2") (pintype "input"))
      (node (ref "R3") (pin "1") (pinfunction "1_1") (pintype "passive"))
      (node (ref "R4") (pin "2") (pinfunction "2_2") (pintype "passive"))
    )
    (net (code "52") (name "Net-(IC1A-OUT)") (class "Default")
      (node (ref "C3") (pin "2") (pinfunction "2_2") (pintype "passive"))
      (node (ref "IC1") (pin "1") (pinfunction "OUT_1") (pintype "output"))
      (node (ref "R11") (pin "1") (pinfunction "1_1") (pintype "passive"))
    )
    (net (code "53") (name "Net-(IC1B-+IN)") (class "Default")
      (node (ref "IC1") (pin "5") (pinfunction "+IN_5") (pintype "input"))
      (node (ref "ICD") (pin "9") (pinfunction "VOUTD_9") (pintype "output"))
    )
    (net (code "54") (name "Net-(IC1B--IN)") (class "Default")
      (node (ref "C2") (pin "1") (pinfunction "1_1") (pintype "passive"))
      (node (ref "IC1") (pin "6") (pinfunction "-IN_6") (pintype "input"))
      (node (ref "R1") (pin "1") (pinfunction "1_1") (pintype "passive"))
      (node (ref "R2") (pin "2") (pinfunction "2_2") (pintype "passive"))
    )
    (net (code "55") (name "Net-(IC1B-OUT)") (class "Default")
      (node (ref "C2") (pin "2") (pinfunction "2_2") (pintype "passive"))
      (node (ref "IC1") (pin "7") (pinfunction "OUT_7") (pintype "output"))
      (node (ref "R5") (pin "1") (pinfunction "1_1") (pintype "passive"))
    )
    (net (code "56") (name "Net-(IC2A-+IN)") (class "Default")
      (node (ref "IC2") (pin "3") (pinfunction "+IN_3") (pintype "input"))
      (node (ref "ICD") (pin "6") (pinfunction "VOUTA_6") (pintype "output"))
    )
    (net (code "57") (name "Net-(IC2A--IN)") (class "Default")
      (node (ref "C7") (pin "1") (pinfunction "1_1") (pintype "passive"))
      (node (ref "IC2") (pin "2") (pinfunction "-IN_2") (pintype "input"))
      (node (ref "R15") (pin "1") (pinfunction "1_1") (pintype "passive"))
      (node (ref "R16") (pin "2") (pinfunction "2_2") (pintype "passive"))
    )
    (net (code "58") (name "Net-(IC2A-OUT)") (class "Default")
      (node (ref "C7") (pin "2") (pinfunction "2_2") (pintype "passive"))
      (node (ref "IC2") (pin "1") (pinfunction "OUT_1") (pintype "output"))
      (node (ref "R14") (pin "1") (pinfunction "1_1") (pintype "passive"))
    )
    (net (code "59") (name "Net-(IC2B-+IN)") (class "Default")
      (node (ref "IC2") (pin "5") (pinfunction "+IN_5") (pintype "input"))
      (node (ref "ICD") (pin "7") (pinfunction "VOUTB_7") (pintype "output"))
    )
    (net (code "60") (name "Net-(IC2B--IN)") (class "Default")
      (node (ref "C4") (pin "1") (pinfunction "1_1") (pintype "passive"))
      (node (ref "IC2") (pin "6") (pinfunction "-IN_6") (pintype "input"))
      (node (ref "R12") (pin "1") (pinfunction "1_1") (pintype "passive"))
      (node (ref "R6") (pin "2") (pinfunction "2_2") (pintype "passive"))
    )
    (net (code "61") (name "Net-(IC2B-OUT)") (class "Default")
      (node (ref "C4") (pin "2") (pinfunction "2_2") (pintype "passive"))
      (node (ref "IC2") (pin "7") (pinfunction "OUT_7") (pintype "output"))
      (node (ref "R13") (pin "1") (pinfunction "1_1") (pintype "passive"))
    )
    (net (code "62") (name "Net-(IC3-AREF)") (class "Default")
      (node (ref "C8") (pin "1") (pinfunction "1_1") (pintype "passive"))
      (node (ref "IC3") (pin "21") (pinfunction "AREF_21") (pintype "passive"))
    )
    (net (code "63") (name "Net-(IC3-PB2(SS{slash}OC1B))") (class "Default")
      (node (ref "IC3") (pin "16") (pinfunction "PB2(SS/OC1B)_16") (pintype "bidirectional"))
      (node (ref "IC4") (pin "14") (pinfunction "FI_14") (pintype "input"))
    )
    (net (code "64") (name "Net-(IC3-PB6(XTAL1{slash}TOSC1))") (class "Default")
      (node (ref "C11") (pin "1") (pinfunction "1_1") (pintype "passive"))
      (node (ref "IC3") (pin "9") (pinfunction "PB6(XTAL1/TOSC1)_9") (pintype "bidirectional"))
      (node (ref "Q1") (pin "2") (pinfunction "2_2") (pintype "passive"))
    )
    (net (code "65") (name "Net-(IC3-PB7(XTAL2{slash}TOSC2))") (class "Default")
      (node (ref "C10") (pin "1") (pinfunction "1_1") (pintype "passive"))
      (node (ref "IC3") (pin "10") (pinfunction "PB7(XTAL2/TOSC2)_10") (pintype "bidirectional"))
      (node (ref "Q1") (pin "1") (pinfunction "1_1") (pintype "passive"))
    )
    (net (code "66") (name "Net-(IC3-PC0(ADC0))") (class "Default")
      (node (ref "IC3") (pin "23") (pinfunction "PC0(ADC0)_23") (pintype "bidirectional"))
      (node (ref "JP102") (pin "1") (pinfunction "1_1") (pintype "passive"))
    )
    (net (code "67") (name "Net-(IC3-PC1(ADC1))") (class "Default")
      (node (ref "IC3") (pin "24") (pinfunction "PC1(ADC1)_24") (pintype "bidirectional"))
      (node (ref "JP102") (pin "2") (pinfunction "2_2") (pintype "passive"))
    )
    (net (code "68") (name "Net-(IC3-PC2(ADC2))") (class "Default")
      (node (ref "IC3") (pin "25") (pinfunction "PC2(ADC2)_25") (pintype "bidirectional"))
      (node (ref "JP102") (pin "5") (pinfunction "5_5") (pintype "passive"))
    )
    (net (code "69") (name "Net-(IC3-PC3(ADC3))") (class "Default")
      (node (ref "IC3") (pin "26") (pinfunction "PC3(ADC3)_26") (pintype "bidirectional"))
      (node (ref "JP102") (pin "7") (pinfunction "7_7") (pintype "passive"))
    )
    (net (code "70") (name "Net-(IC3-PC4(ADC4{slash}SDA))") (class "Default")
      (node (ref "IC3") (pin "27") (pinfunction "PC4(ADC4/SDA)_27") (pintype "bidirectional"))
      (node (ref "ICD") (pin "3") (pinfunction "SDA_3") (pintype "bidirectional"))
      (node (ref "R10") (pin "1") (pinfunction "1_1") (pintype "passive"))
    )
    (net (code "71") (name "Net-(IC3-PC5(ADC5{slash}SCL))") (class "Default")
      (node (ref "IC3") (pin "28") (pinfunction "PC5(ADC5/SCL)_28") (pintype "bidirectional"))
      (node (ref "ICD") (pin "2") (pinfunction "SCL_2") (pintype "input"))
      (node (ref "R9") (pin "1") (pinfunction "1_1") (pintype "passive"))
    )
    (net (code "72") (name "Net-(IC3-PD0(RXD))") (class "Default")
      (node (ref "IC3") (pin "2") (pinfunction "PD0(RXD)_2") (pintype "bidirectional"))
      (node (ref "OK1") (pin "6") (pinfunction "VO_6") (pintype "passive"))
      (node (ref "R18") (pin "2") (pinfunction "2_2") (pintype "passive"))
    )
    (net (code "73") (name "Net-(IC3-PD2(INT0))") (class "Default")
      (node (ref "IC3") (pin "4") (pinfunction "PD2(INT0)_4") (pintype "bidirectional"))
      (node (ref "IC4") (pin "3") (pinfunction "AI_3") (pintype "input"))
    )
    (net (code "74") (name "Net-(IC3-PD3(INT1))") (class "Default")
      (node (ref "IC3") (pin "5") (pinfunction "PD3(INT1)_5") (pintype "bidirectional"))
      (node (ref "IC4") (pin "5") (pinfunction "BI_5") (pintype "input"))
    )
    (net (code "75") (name "Net-(IC3-PD4(XCK{slash}T0))") (class "Default")
      (node (ref "IC3") (pin "6") (pinfunction "PD4(XCK/T0)_6") (pintype "bidirectional"))
      (node (ref "IC4") (pin "7") (pinfunction "CI_7") (pintype "input"))
    )
    (net (code "76") (name "Net-(IC3-PD5(T1))") (class "Default")
      (node (ref "IC3") (pin "11") (pinfunction "PD5(T1)_11") (pintype "bidirectional"))
      (node (ref "IC4") (pin "9") (pinfunction "DI_9") (pintype "input"))
    )
    (net (code "77") (name "Net-(IC3-PD6(AIN0))") (class "Default")
      (node (ref "IC3") (pin "12") (pinfunction "PD6(AIN0)_12") (pintype "bidirectional"))
      (node (ref "IC4") (pin "11") (pinfunction "EI_11") (pintype "input"))
    )
    (net (code "78") (name "Net-(ICD-RDY{slash}*BSY)") (class "Default")
      (node (ref "ICD") (pin "5") (pinfunction "RDY/*BSY_5") (pintype "output"))
      (node (ref "R7") (pin "1") (pinfunction "1_1") (pintype "passive"))
    )
    (net (code "79") (name "Net-(ICD-VDD)") (class "Default")
      (node (ref "C6") (pin "1") (pinfunction "1_1") (pintype "passive"))
      (node (ref "ICD") (pin "1") (pinfunction "VDD_1") (pintype "power_in"))
      (node (ref "L1") (pin "2") (pinfunction "2_2") (pintype "passive"))
    )
    (net (code "80") (name "Net-(MIDI-Pad4)") (class "Default")
      (node (ref "MIDI") (pin "4") (pinfunction "4_4") (pintype "passive"))
      (node (ref "R20") (pin "1") (pinfunction "1_1") (pintype "passive"))
    )
    (net (code "81") (name "Net-(OK1-VB)") (class "Default")
      (node (ref "OK1") (pin "7") (pinfunction "VB_7") (pintype "passive"))
      (node (ref "R19") (pin "1") (pinfunction "1_1") (pintype "passive"))
    )
    (net (code "82") (name "Net-(R100-Pad1)") (class "Default")
      (node (ref "R100") (pin "1") (pinfunction "1_1") (pintype "passive"))
      (node (ref "ST/SP") (pin "TIP") (pinfunction "TIP_TIP") (pintype "passive"))
    )
    (net (code "83") (name "Net-(U$1-1)") (class "Default")
      (node (ref "JP101") (pin "5") (pinfunction "5_5") (pintype "passive"))
      (node (ref "U$1") (pin "P$1") (pinfunction "1_P$1") (pintype "passive"))
    )
    (net (code "84") (name "RESET") (class "Default")
      (node (ref "IC3") (pin "1") (pinfunction "PC6(/RESET)_1") (pintype "bidirectional"))
      (node (ref "ICSP") (pin "5") (pinfunction "5_5") (pintype "passive"))
      (node (ref "R8") (pin "2") (pinfunction "2_2") (pintype "passive"))
    )
    (net (code "85") (name "START{slash}STOP_COMP") (class "Default")
      (node (ref "IC4") (pin "15") (pinfunction "FO_15") (pintype "output"))
      (node (ref "JP2") (pin "10") (pinfunction "10_10") (pintype "passive"))
    )
    (net (code "86") (name "START{slash}STOP_CONT") (class "Default")
      (node (ref "JP100") (pin "9") (pinfunction "9_9") (pintype "passive"))
      (node (ref "R100") (pin "2") (pinfunction "2_2") (pintype "passive"))
      (node (ref "R101") (pin "1") (pinfunction "1_1") (pintype "passive"))
    )
    (net (code "87") (name "V+") (class "Default")
      (node (ref "C1") (pin "1") (pinfunction "1_1") (pintype "passive"))
      (node (ref "C13") (pin "1") (pinfunction "1_1") (pintype "passive"))
      (node (ref "C16") (pin "+") (pinfunction "+_+") (pintype "passive"))
      (node (ref "C5") (pin "1") (pinfunction "1_1") (pintype "passive"))
      (node (ref "D10") (pin "C") (pinfunction "C_C") (pintype "passive"))
      (node (ref "IC1") (pin "8") (pinfunction "V+_8") (pintype "power_in"))
      (node (ref "IC2") (pin "8") (pinfunction "V+_8") (pintype "power_in"))
      (node (ref "IC4") (pin "16") (pinfunction "VDD_16") (pintype "power_in"))
    )
    (net (code "88") (name "V-") (class "Default")
      (node (ref "C1") (pin "2") (pinfunction "2_2") (pintype "passive"))
      (node (ref "C14") (pin "2") (pinfunction "2_2") (pintype "passive"))
      (node (ref "C15") (pin "-") (pinfunction "-_-") (pintype "passive"))
      (node (ref "C5") (pin "2") (pinfunction "2_2") (pintype "passive"))
      (node (ref "FERRITE-") (pin "2") (pinfunction "2_2") (pintype "passive"))
      (node (ref "IC1") (pin "4") (pinfunction "V-_4") (pintype "power_in"))
      (node (ref "IC2") (pin "4") (pinfunction "V-_4") (pintype "power_in"))
    )
    (net (code "89") (name "unconnected-(CLK-SWITCH-PadDESC)") (class "Default")
      (node (ref "CLK") (pin "DESC") (pinfunction "SWITCH_DESC") (pintype "passive"))
    )
    (net (code "90") (name "unconnected-(CV_A-SWITCH-PadDESC)") (class "Default")
      (node (ref "CV_A") (pin "DESC") (pinfunction "SWITCH_DESC") (pintype "passive"))
    )
    (net (code "91") (name "unconnected-(CV_B-SWITCH-PadDESC)") (class "Default")
      (node (ref "CV_B") (pin "DESC") (pinfunction "SWITCH_DESC") (pintype "passive"))
    )
    (net (code "92") (name "unconnected-(CV_C-SWITCH-PadDESC)") (class "Default")
      (node (ref "CV_C") (pin "DESC") (pinfunction "SWITCH_DESC") (pintype "passive"))
    )
    (net (code "93") (name "unconnected-(CV_D-SWITCH-PadDESC)") (class "Default")
      (node (ref "CV_D") (pin "DESC") (pinfunction "SWITCH_DESC") (pintype "passive"))
    )
    (net (code "94") (name "unconnected-(GATE_A-SWITCH-PadDESC)") (class "Default")
      (node (ref "GATE_A") (pin "DESC") (pinfunction "SWITCH_DESC") (pintype "passive"))
    )
    (net (code "95") (name "unconnected-(GATE_B-SWITCH-PadDESC)") (class "Default")
      (node (ref "GATE_B") (pin "DESC") (pinfunction "SWITCH_DESC") (pintype "passive"))
    )
    (net (code "96") (name "unconnected-(GATE_C-SWITCH-PadDESC)") (class "Default")
      (node (ref "GATE_C") (pin "DESC") (pinfunction "SWITCH_DESC") (pintype "passive"))
    )
    (net (code "97") (name "unconnected-(GATE_D-SWITCH-PadDESC)") (class "Default")
      (node (ref "GATE_D") (pin "DESC") (pinfunction "SWITCH_DESC") (pintype "passive"))
    )
    (net (code "98") (name "unconnected-(IC3-PB0(ICP)-Pad14)") (class "Default")
      (node (ref "IC3") (pin "14") (pinfunction "PB0(ICP)_14") (pintype "bidirectional"))
    )
    (net (code "99") (name "unconnected-(JP102-Pad6)") (class "Default")
      (node (ref "JP102") (pin "6") (pinfunction "6_6") (pintype "passive"))
    )
    (net (code "100") (name "unconnected-(MIDI-Pad1)") (class "Default")
      (node (ref "MIDI") (pin "1") (pinfunction "1_1") (pintype "passive"))
    )
    (net (code "101") (name "unconnected-(MIDI-Pad2)") (class "Default")
      (node (ref "MIDI") (pin "2") (pinfunction "2_2") (pintype "passive"))
    )
    (net (code "102") (name "unconnected-(MIDI-Pad3)") (class "Default")
      (node (ref "MIDI") (pin "3") (pinfunction "3_3") (pintype "passive"))
    )
    (net (code "103") (name "unconnected-(ST/SP-SWITCH-PadDESC)") (class "Default")
      (node (ref "ST/SP") (pin "DESC") (pinfunction "SWITCH_DESC") (pintype "passive"))
    )
    (net (code "104") (name "unconnected-(U$2-Pad5)") (class "Default")
      (node (ref "U$2") (pin "5") (pinfunction "5_5") (pintype "passive"))
    )
    (net (code "105") (name "unconnected-(U$2-Pad6)") (class "Default")
      (node (ref "U$2") (pin "6") (pinfunction "6_6") (pintype "passive"))
    )
    (net (code "106") (name "unconnected-(U$2-Pad13)") (class "Default")
      (node (ref "U$2") (pin "13") (pinfunction "13_13") (pintype "passive"))
    )
    (net (code "107") (name "unconnected-(U$2-Pad14)") (class "Default")
      (node (ref "U$2") (pin "14") (pinfunction "14_14") (pintype "passive"))
    )
    (net (code "108") (name "unconnected-(U$2-Pad15)") (class "Default")
      (node (ref "U$2") (pin "15") (pinfunction "15_15") (pintype "passive"))
    )
    (net (code "109") (name "unconnected-(U$2-Pad16)") (class "Default")
      (node (ref "U$2") (pin "16") (pinfunction "16_16") (pintype "passive"))
    )
  )
)
